# nled-triangle-ap102-pixel-panel-v1a.net
KiCad netlist of a schematic drawn in EAGLE
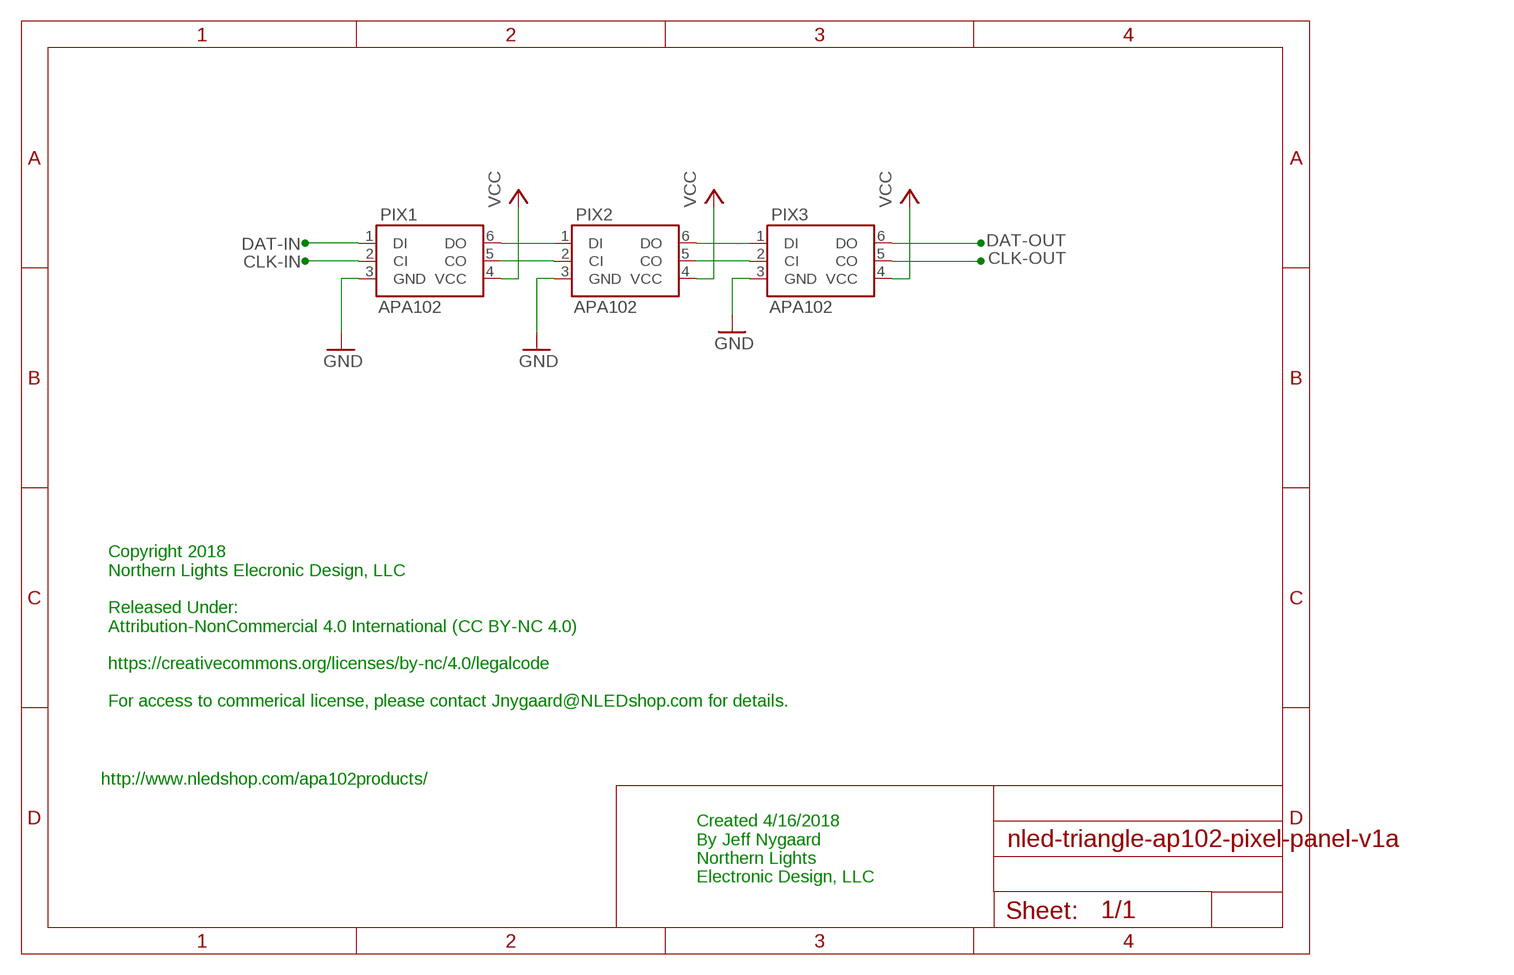
[diagram p0: schematic, sheet 1]

(export (version "E")
  (design (tool "Eeschema 10.0.6"))
  (components
    (comp (ref "PIX1")
      (value "APA102")
      (footprint "eagle-import:APA102")
      (libsource (lib "eagle-import") (part "APA102"))
    )
    (comp (ref "PIX2")
      (value "APA102")
      (footprint "eagle-import:APA102")
      (libsource (lib "eagle-import") (part "APA102"))
    )
    (comp (ref "PIX3")
      (value "APA102")
      (footprint "eagle-import:APA102")
      (libsource (lib "eagle-import") (part "APA102"))
    )
  )
  (nets
    (net (code "1") (name "/CLK-IN") (class "Default")
      (node (ref "PIX1") (pin "2") (pinfunction "CI_2") (pintype "bidirectional"))
    )
    (net (code "2") (name "/CLK-OUT") (class "Default")
      (node (ref "PIX3") (pin "5") (pinfunction "CO_5") (pintype "bidirectional"))
    )
    (net (code "3") (name "/DAT-IN") (class "Default")
      (node (ref "PIX1") (pin "1") (pinfunction "DI_1") (pintype "bidirectional"))
    )
    (net (code "4") (name "/DAT-OUT") (class "Default")
      (node (ref "PIX3") (pin "6") (pinfunction "DO_6") (pintype "bidirectional"))
    )
    (net (code "5") (name "GND") (class "Default")
      (node (ref "PIX1") (pin "3") (pinfunction "GND_3") (pintype "bidirectional"))
      (node (ref "PIX2") (pin "3") (pinfunction "GND_3") (pintype "bidirectional"))
      (node (ref "PIX3") (pin "3") (pinfunction "GND_3") (pintype "bidirectional"))
    )
    (net (code "6") (name "Net-(PIX1-CO)") (class "Default")
      (node (ref "PIX1") (pin "5") (pinfunction "CO_5") (pintype "bidirectional"))
      (node (ref "PIX2") (pin "2") (pinfunction "CI_2") (pintype "bidirectional"))
    )
    (net (code "7") (name "Net-(PIX1-DO)") (class "Default")
      (node (ref "PIX1") (pin "6") (pinfunction "DO_6") (pintype "bidirectional"))
      (node (ref "PIX2") (pin "1") (pinfunction "DI_1") (pintype "bidirectional"))
    )
    (net (code "8") (name "Net-(PIX2-CO)") (class "Default")
      (node (ref "PIX2") (pin "5") (pinfunction "CO_5") (pintype "bidirectional"))
      (node (ref "PIX3") (pin "2") (pinfunction "CI_2") (pintype "bidirectional"))
    )
    (net (code "9") (name "Net-(PIX2-DO)") (class "Default")
      (node (ref "PIX2") (pin "6") (pinfunction "DO_6") (pintype "bidirectional"))
      (node (ref "PIX3") (pin "1") (pinfunction "DI_1") (pintype "bidirectional"))
    )
    (net (code "10") (name "VCC") (class "Default")
      (node (ref "PIX1") (pin "4") (pinfunction "VCC_4") (pintype "bidirectional"))
      (node (ref "PIX2") (pin "4") (pinfunction "VCC_4") (pintype "bidirectional"))
      (node (ref "PIX3") (pin "4") (pinfunction "VCC_4") (pintype "bidirectional"))
    )
  )
)
